# 1.net
KiCad netlist of a schematic drawn in EAGLE
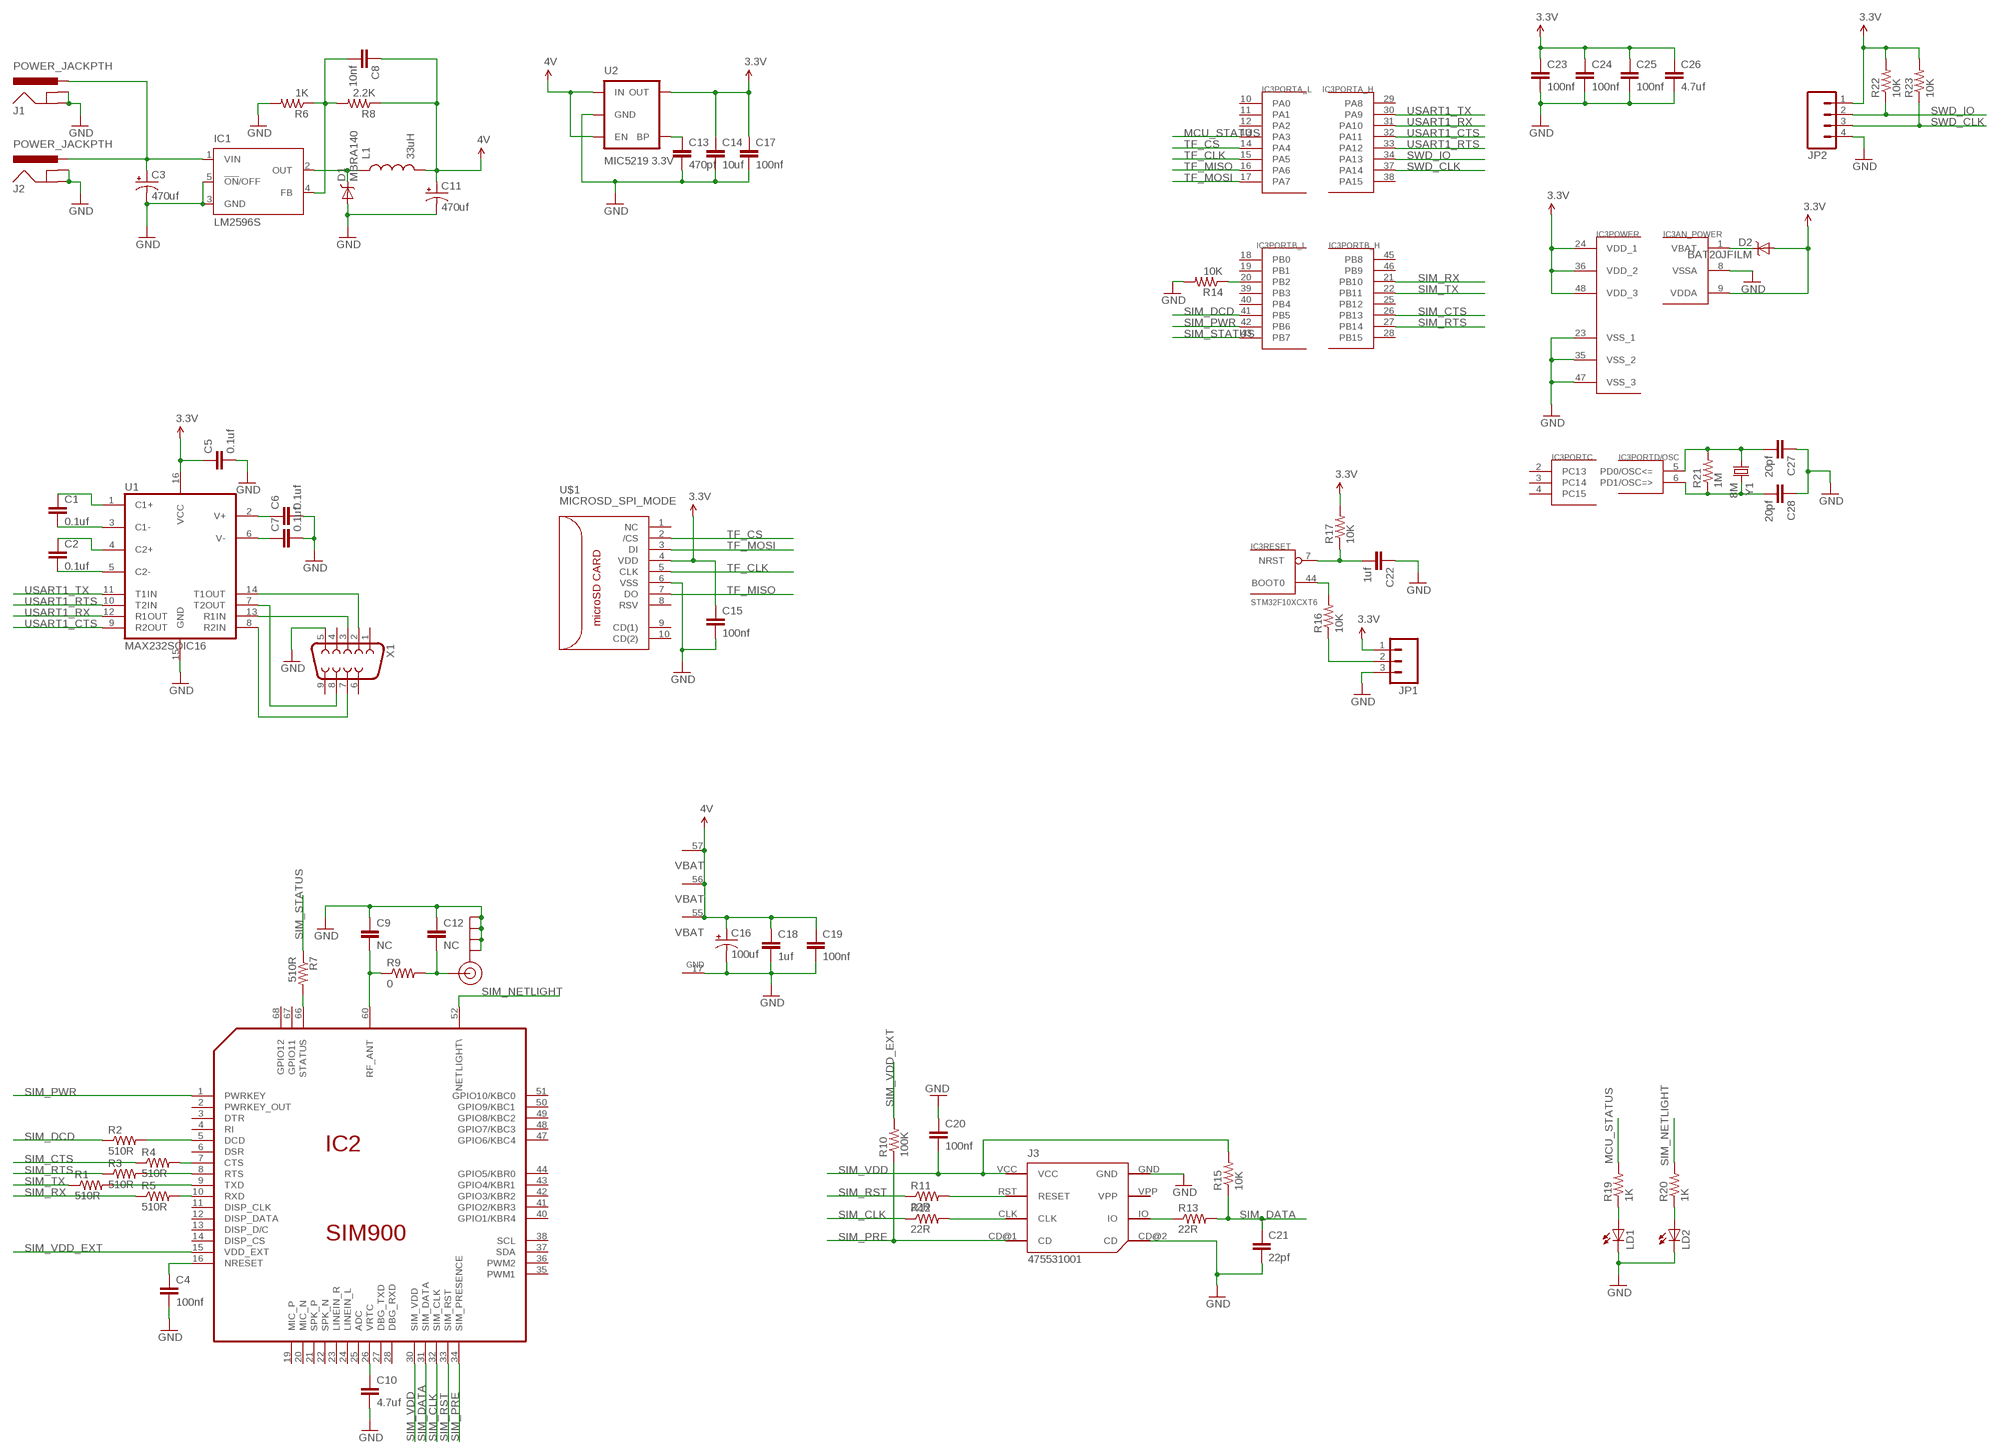
[diagram p0: schematic, sheet 1]

(export (version "E")
  (design (tool "Eeschema 10.0.6"))
  (components
    (comp (ref "C1")
      (value "0.1uf")
      (footprint "eagle-import:0603-CAP")
      (libsource (lib "eagle-import") (part "CAP0603-CAP"))
    )
    (comp (ref "C2")
      (value "0.1uf")
      (footprint "eagle-import:0603-CAP")
      (libsource (lib "eagle-import") (part "CAP0603-CAP"))
    )
    (comp (ref "C3")
      (value "470uf")
      (footprint "eagle-import:PANASONIC_G")
      (libsource (lib "eagle-import") (part "CAP_POLG"))
    )
    (comp (ref "C4")
      (value "100nf")
      (footprint "eagle-import:0603-CAP")
      (libsource (lib "eagle-import") (part "CAP0603-CAP"))
    )
    (comp (ref "C5")
      (value "0.1uf")
      (footprint "eagle-import:0603-CAP")
      (libsource (lib "eagle-import") (part "CAP0603-CAP"))
    )
    (comp (ref "C6")
      (value "0.1uf")
      (footprint "eagle-import:0603-CAP")
      (libsource (lib "eagle-import") (part "CAP0603-CAP"))
    )
    (comp (ref "C7")
      (value "0.1uf")
      (footprint "eagle-import:0603-CAP")
      (libsource (lib "eagle-import") (part "CAP0603-CAP"))
    )
    (comp (ref "C8")
      (value "10nf")
      (footprint "eagle-import:0603-CAP")
      (libsource (lib "eagle-import") (part "CAP0603-CAP"))
    )
    (comp (ref "C9")
      (value "NC")
      (footprint "eagle-import:0603-CAP")
      (libsource (lib "eagle-import") (part "CAP0603-CAP"))
    )
    (comp (ref "C10")
      (value "4.7uf")
      (footprint "eagle-import:0603-CAP")
      (libsource (lib "eagle-import") (part "CAP0603-CAP"))
    )
    (comp (ref "C11")
      (value "470uf")
      (footprint "eagle-import:PANASONIC_G")
      (libsource (lib "eagle-import") (part "CAP_POLG"))
    )
    (comp (ref "C12")
      (value "NC")
      (footprint "eagle-import:0603-CAP")
      (libsource (lib "eagle-import") (part "CAP0603-CAP"))
    )
    (comp (ref "C13")
      (value "470pf")
      (footprint "eagle-import:0603-CAP")
      (libsource (lib "eagle-import") (part "CAP0603-CAP"))
    )
    (comp (ref "C14")
      (value "10uf")
      (footprint "eagle-import:0603-CAP")
      (libsource (lib "eagle-import") (part "CAP0603-CAP"))
    )
    (comp (ref "C15")
      (value "100nf")
      (footprint "eagle-import:0603-CAP")
      (libsource (lib "eagle-import") (part "CAP0603-CAP"))
    )
    (comp (ref "C16")
      (value "100uf")
      (footprint "eagle-import:EIA6032")
      (libsource (lib "eagle-import") (part "SparkFun-Passives_CAP_POL6032"))
    )
    (comp (ref "C17")
      (value "100nf")
      (footprint "eagle-import:0603-CAP")
      (libsource (lib "eagle-import") (part "CAP0603-CAP"))
    )
    (comp (ref "C18")
      (value "1uf")
      (footprint "eagle-import:0603-CAP")
      (libsource (lib "eagle-import") (part "CAP0603-CAP"))
    )
    (comp (ref "C19")
      (value "100nf")
      (footprint "eagle-import:0603-CAP")
      (libsource (lib "eagle-import") (part "CAP0603-CAP"))
    )
    (comp (ref "C20")
      (value "100nf")
      (footprint "eagle-import:0603-CAP")
      (libsource (lib "eagle-import") (part "CAP0603-CAP"))
    )
    (comp (ref "C21")
      (value "22pf")
      (footprint "eagle-import:0603-CAP")
      (libsource (lib "eagle-import") (part "CAP0603-CAP"))
    )
    (comp (ref "C22")
      (value "1uf")
      (footprint "eagle-import:0603-CAP")
      (libsource (lib "eagle-import") (part "CAP0603-CAP"))
    )
    (comp (ref "C23")
      (value "100nf")
      (footprint "eagle-import:0603-CAP")
      (libsource (lib "eagle-import") (part "CAP0603-CAP"))
    )
    (comp (ref "C24")
      (value "100nf")
      (footprint "eagle-import:0603-CAP")
      (libsource (lib "eagle-import") (part "CAP0603-CAP"))
    )
    (comp (ref "C25")
      (value "100nf")
      (footprint "eagle-import:0603-CAP")
      (libsource (lib "eagle-import") (part "CAP0603-CAP"))
    )
    (comp (ref "C26")
      (value "4.7uf")
      (footprint "eagle-import:0603-CAP")
      (libsource (lib "eagle-import") (part "CAP0603-CAP"))
    )
    (comp (ref "C27")
      (value "20pf")
      (footprint "eagle-import:0603-CAP")
      (libsource (lib "eagle-import") (part "CAP0603-CAP"))
    )
    (comp (ref "C28")
      (value "20pf")
      (footprint "eagle-import:0603-CAP")
      (libsource (lib "eagle-import") (part "CAP0603-CAP"))
    )
    (comp (ref "D1")
      (value "MBRA140")
      (footprint "eagle-import:SMA-DIODE")
      (libsource (lib "eagle-import") (part "MBRA140"))
    )
    (comp (ref "D2")
      (value "BAT20JFILM")
      (footprint "eagle-import:SOD-323")
      (libsource (lib "eagle-import") (part "BAT20JFILM"))
    )
    (comp (ref "IC1")
      (value "LM2596S")
      (footprint "eagle-import:TO263-5")
      (libsource (lib "eagle-import") (part "LM2596S"))
    )
    (comp (ref "IC2")
      (value "SIM900")
      (footprint "eagle-import:SIM900")
      (libsource (lib "eagle-import") (part "SIM900"))
    )
    (comp (ref "IC3")
      (value "STM32F10XCXT6")
      (footprint "eagle-import:TQFP48")
      (libsource (lib "eagle-import") (part "STM32F10XCXT6"))
    )
    (comp (ref "J$1")
      (value "SMA_EDGE")
      (footprint "eagle-import:SMA-EDGE")
      (libsource (lib "eagle-import") (part "SMA_EDGE"))
    )
    (comp (ref "J1")
      (value "POWER_JACKPTH")
      (footprint "eagle-import:POWER_JACK_PTH")
      (libsource (lib "eagle-import") (part "POWER_JACKPTH"))
    )
    (comp (ref "J2")
      (value "POWER_JACKPTH")
      (footprint "eagle-import:POWER_JACK_PTH")
      (libsource (lib "eagle-import") (part "POWER_JACKPTH"))
    )
    (comp (ref "J3")
      (value "475531001")
      (footprint "eagle-import:475531001")
      (libsource (lib "eagle-import") (part "475531001"))
    )
    (comp (ref "JP1")
      (value "M03PTH")
      (footprint "eagle-import:1X03")
      (libsource (lib "eagle-import") (part "M03PTH"))
    )
    (comp (ref "JP2")
      (value "M04PTH")
      (footprint "eagle-import:1X04")
      (libsource (lib "eagle-import") (part "M04PTH"))
    )
    (comp (ref "L1")
      (value "33uH")
      (footprint "eagle-import:CR75")
      (libsource (lib "eagle-import") (part "INDUCTOR68UH-1A"))
    )
    (comp (ref "LD1")
      (value "LEDCHIP-LED0805")
      (footprint "eagle-import:CHIP-LED0805")
      (libsource (lib "eagle-import") (part "LEDCHIP-LED0805"))
    )
    (comp (ref "LD2")
      (value "LEDCHIP-LED0805")
      (footprint "eagle-import:CHIP-LED0805")
      (libsource (lib "eagle-import") (part "LEDCHIP-LED0805"))
    )
    (comp (ref "R1")
      (value "510R")
      (footprint "eagle-import:0603-RES")
      (libsource (lib "eagle-import") (part "RESISTOR0603-RES"))
    )
    (comp (ref "R2")
      (value "510R")
      (footprint "eagle-import:0603-RES")
      (libsource (lib "eagle-import") (part "RESISTOR0603-RES"))
    )
    (comp (ref "R3")
      (value "510R")
      (footprint "eagle-import:0603-RES")
      (libsource (lib "eagle-import") (part "RESISTOR0603-RES"))
    )
    (comp (ref "R4")
      (value "510R")
      (footprint "eagle-import:0603-RES")
      (libsource (lib "eagle-import") (part "RESISTOR0603-RES"))
    )
    (comp (ref "R5")
      (value "510R")
      (footprint "eagle-import:0603-RES")
      (libsource (lib "eagle-import") (part "RESISTOR0603-RES"))
    )
    (comp (ref "R6")
      (value "1K")
      (footprint "eagle-import:0603-RES")
      (libsource (lib "eagle-import") (part "RESISTOR0603-RES"))
    )
    (comp (ref "R7")
      (value "510R")
      (footprint "eagle-import:0603-RES")
      (libsource (lib "eagle-import") (part "RESISTOR0603-RES"))
    )
    (comp (ref "R8")
      (value "2.2K")
      (footprint "eagle-import:0603-RES")
      (libsource (lib "eagle-import") (part "RESISTOR0603-RES"))
    )
    (comp (ref "R9")
      (value "0")
      (footprint "eagle-import:0603-RES")
      (libsource (lib "eagle-import") (part "1M-1%"))
    )
    (comp (ref "R10")
      (value "100K")
      (footprint "eagle-import:0603-RES")
      (libsource (lib "eagle-import") (part "1M-1%"))
    )
    (comp (ref "R11")
      (value "22R")
      (footprint "eagle-import:0603-RES")
      (libsource (lib "eagle-import") (part "1M-1%"))
    )
    (comp (ref "R12")
      (value "22R")
      (footprint "eagle-import:0603-RES")
      (libsource (lib "eagle-import") (part "1M-1%"))
    )
    (comp (ref "R13")
      (value "22R")
      (footprint "eagle-import:0603-RES")
      (libsource (lib "eagle-import") (part "1M-1%"))
    )
    (comp (ref "R14")
      (value "10K")
      (footprint "eagle-import:0603-RES")
      (libsource (lib "eagle-import") (part "1M-1%"))
    )
    (comp (ref "R15")
      (value "10K")
      (footprint "eagle-import:0603-RES")
      (libsource (lib "eagle-import") (part "1M-1%"))
    )
    (comp (ref "R16")
      (value "10K")
      (footprint "eagle-import:0603-RES")
      (libsource (lib "eagle-import") (part "RESISTOR0603-RES"))
    )
    (comp (ref "R17")
      (value "10K")
      (footprint "eagle-import:0603-RES")
      (libsource (lib "eagle-import") (part "RESISTOR0603-RES"))
    )
    (comp (ref "R19")
      (value "1K")
      (footprint "eagle-import:0603-RES")
      (libsource (lib "eagle-import") (part "RESISTOR0603-RES"))
    )
    (comp (ref "R20")
      (value "1K")
      (footprint "eagle-import:0603-RES")
      (libsource (lib "eagle-import") (part "RESISTOR0603-RES"))
    )
    (comp (ref "R21")
      (value "1M")
      (footprint "eagle-import:0603-RES")
      (libsource (lib "eagle-import") (part "1M-1%"))
    )
    (comp (ref "R22")
      (value "10K")
      (footprint "eagle-import:0603-RES")
      (libsource (lib "eagle-import") (part "1M-1%"))
    )
    (comp (ref "R23")
      (value "10K")
      (footprint "eagle-import:0603-RES")
      (libsource (lib "eagle-import") (part "1M-1%"))
    )
    (comp (ref "U$1")
      (value "MICROSD_SPI_MODE")
      (footprint "eagle-import:MICRO_SD_CONNECTOR")
      (libsource (lib "eagle-import") (part "MICROSD_SPI_MODE"))
    )
    (comp (ref "U1")
      (value "MAX232SOIC16")
      (footprint "eagle-import:SO016")
      (libsource (lib "eagle-import") (part "MAX232SOIC16"))
    )
    (comp (ref "U2")
      (value "MIC5219 3.3V")
      (footprint "eagle-import:SOT23-5")
      (libsource (lib "eagle-import") (part "V_REG_MIC52193.3V"))
    )
    (comp (ref "X1")
      (value "DB9FEMALE")
      (footprint "eagle-import:DB9")
      (libsource (lib "eagle-import") (part "DB9FEMALE"))
    )
    (comp (ref "Y1")
      (value "8M")
      (footprint "eagle-import:HC49US")
      (libsource (lib "eagle-import") (part "CRYSTALHC49US"))
    )
  )
  (nets
    (net (code "1") (name "/MCU_STATUS") (class "Default")
      (node (ref "IC3") (pin "13") (pinfunction "PA3_13") (pintype "bidirectional"))
      (node (ref "R19") (pin "2") (pinfunction "2_2") (pintype "passive"))
    )
    (net (code "2") (name "/SIM_CLK") (class "Default")
      (node (ref "IC2") (pin "32") (pinfunction "SIM_CLK_32") (pintype "bidirectional"))
      (node (ref "R12") (pin "1") (pinfunction "1_1") (pintype "passive"))
    )
    (net (code "3") (name "/SIM_CTS") (class "Default")
      (node (ref "IC3") (pin "26") (pinfunction "PB13_26") (pintype "bidirectional"))
      (node (ref "R4") (pin "1") (pinfunction "1_1") (pintype "passive"))
    )
    (net (code "4") (name "/SIM_DATA") (class "Default")
      (node (ref "C21") (pin "1") (pinfunction "1_1") (pintype "passive"))
      (node (ref "IC2") (pin "31") (pinfunction "SIM_DATA_31") (pintype "bidirectional"))
      (node (ref "R13") (pin "2") (pinfunction "2_2") (pintype "passive"))
      (node (ref "R15") (pin "1") (pinfunction "1_1") (pintype "passive"))
    )
    (net (code "5") (name "/SIM_DCD") (class "Default")
      (node (ref "IC3") (pin "41") (pinfunction "PB5_41") (pintype "bidirectional"))
      (node (ref "R2") (pin "1") (pinfunction "1_1") (pintype "passive"))
    )
    (net (code "6") (name "/SIM_NETLIGHT") (class "Default")
      (node (ref "IC2") (pin "52") (pinfunction "NETLIGHT\\_52") (pintype "bidirectional"))
      (node (ref "R20") (pin "2") (pinfunction "2_2") (pintype "passive"))
    )
    (net (code "7") (name "/SIM_PRE") (class "Default")
      (node (ref "IC2") (pin "34") (pinfunction "SIM_PRESENCE_34") (pintype "bidirectional"))
      (node (ref "J3") (pin "CD@1") (pinfunction "CD_CD@1") (pintype "bidirectional"))
      (node (ref "R10") (pin "1") (pinfunction "1_1") (pintype "passive"))
    )
    (net (code "8") (name "/SIM_PWR") (class "Default")
      (node (ref "IC2") (pin "1") (pinfunction "PWRKEY_1") (pintype "bidirectional"))
      (node (ref "IC3") (pin "42") (pinfunction "PB6_42") (pintype "bidirectional"))
    )
    (net (code "9") (name "/SIM_RST") (class "Default")
      (node (ref "IC2") (pin "33") (pinfunction "SIM_RST_33") (pintype "bidirectional"))
      (node (ref "R11") (pin "1") (pinfunction "1_1") (pintype "passive"))
    )
    (net (code "10") (name "/SIM_RTS") (class "Default")
      (node (ref "IC3") (pin "27") (pinfunction "PB14_27") (pintype "bidirectional"))
      (node (ref "R3") (pin "1") (pinfunction "1_1") (pintype "passive"))
    )
    (net (code "11") (name "/SIM_RX") (class "Default")
      (node (ref "IC3") (pin "21") (pinfunction "PB10_21") (pintype "bidirectional"))
      (node (ref "R5") (pin "1") (pinfunction "1_1") (pintype "passive"))
    )
    (net (code "12") (name "/SIM_STATUS") (class "Default")
      (node (ref "IC3") (pin "43") (pinfunction "PB7_43") (pintype "bidirectional"))
      (node (ref "R7") (pin "1") (pinfunction "1_1") (pintype "passive"))
    )
    (net (code "13") (name "/SIM_TX") (class "Default")
      (node (ref "IC3") (pin "22") (pinfunction "PB11_22") (pintype "bidirectional"))
      (node (ref "R1") (pin "1") (pinfunction "1_1") (pintype "passive"))
    )
    (net (code "14") (name "/SIM_VDD") (class "Default")
      (node (ref "C20") (pin "2") (pinfunction "2_2") (pintype "passive"))
      (node (ref "IC2") (pin "30") (pinfunction "SIM_VDD_30") (pintype "bidirectional"))
      (node (ref "J3") (pin "VCC") (pinfunction "VCC_VCC") (pintype "bidirectional"))
      (node (ref "R15") (pin "2") (pinfunction "2_2") (pintype "passive"))
    )
    (net (code "15") (name "/SIM_VDD_EXT") (class "Default")
      (node (ref "IC2") (pin "15") (pinfunction "VDD_EXT_15") (pintype "bidirectional"))
      (node (ref "R10") (pin "2") (pinfunction "2_2") (pintype "passive"))
    )
    (net (code "16") (name "/SWD_CLK") (class "Default")
      (node (ref "IC3") (pin "37") (pinfunction "PA14_37") (pintype "bidirectional"))
      (node (ref "JP2") (pin "3") (pinfunction "3_3") (pintype "passive"))
      (node (ref "R23") (pin "1") (pinfunction "1_1") (pintype "passive"))
    )
    (net (code "17") (name "/SWD_IO") (class "Default")
      (node (ref "IC3") (pin "34") (pinfunction "PA13_34") (pintype "bidirectional"))
      (node (ref "JP2") (pin "2") (pinfunction "2_2") (pintype "passive"))
      (node (ref "R22") (pin "1") (pinfunction "1_1") (pintype "passive"))
    )
    (net (code "18") (name "/TF_CLK") (class "Default")
      (node (ref "IC3") (pin "15") (pinfunction "PA5_15") (pintype "bidirectional"))
      (node (ref "U$1") (pin "5") (pinfunction "CLK_5") (pintype "bidirectional"))
    )
    (net (code "19") (name "/TF_CS") (class "Default")
      (node (ref "IC3") (pin "14") (pinfunction "PA4_14") (pintype "bidirectional"))
      (node (ref "U$1") (pin "2") (pinfunction "/CS_2") (pintype "bidirectional"))
    )
    (net (code "20") (name "/TF_MISO") (class "Default")
      (node (ref "IC3") (pin "16") (pinfunction "PA6_16") (pintype "bidirectional"))
      (node (ref "U$1") (pin "7") (pinfunction "DO_7") (pintype "bidirectional"))
    )
    (net (code "21") (name "/TF_MOSI") (class "Default")
      (node (ref "IC3") (pin "17") (pinfunction "PA7_17") (pintype "bidirectional"))
      (node (ref "U$1") (pin "3") (pinfunction "DI_3") (pintype "bidirectional"))
    )
    (net (code "22") (name "/USART1_CTS") (class "Default")
      (node (ref "IC3") (pin "32") (pinfunction "PA11_32") (pintype "bidirectional"))
      (node (ref "U1") (pin "9") (pinfunction "R2OUT_9") (pintype "output"))
    )
    (net (code "23") (name "/USART1_RTS") (class "Default")
      (node (ref "IC3") (pin "33") (pinfunction "PA12_33") (pintype "bidirectional"))
      (node (ref "U1") (pin "10") (pinfunction "T2IN_10") (pintype "input"))
    )
    (net (code "24") (name "/USART1_RX") (class "Default")
      (node (ref "IC3") (pin "31") (pinfunction "PA10_31") (pintype "bidirectional"))
      (node (ref "U1") (pin "12") (pinfunction "R1OUT_12") (pintype "output"))
    )
    (net (code "25") (name "/USART1_TX") (class "Default")
      (node (ref "IC3") (pin "30") (pinfunction "PA9_30") (pintype "bidirectional"))
      (node (ref "U1") (pin "11") (pinfunction "T1IN_11") (pintype "input"))
    )
    (net (code "26") (name "3.3V") (class "Default")
      (node (ref "C14") (pin "1") (pinfunction "1_1") (pintype "passive"))
      (node (ref "C15") (pin "1") (pinfunction "1_1") (pintype "passive"))
      (node (ref "C17") (pin "1") (pinfunction "1_1") (pintype "passive"))
      (node (ref "C23") (pin "1") (pinfunction "1_1") (pintype "passive"))
      (node (ref "C24") (pin "1") (pinfunction "1_1") (pintype "passive"))
      (node (ref "C25") (pin "1") (pinfunction "1_1") (pintype "passive"))
      (node (ref "C26") (pin "1") (pinfunction "1_1") (pintype "passive"))
      (node (ref "C5") (pin "1") (pinfunction "1_1") (pintype "passive"))
      (node (ref "D2") (pin "2") (pinfunction "A_2") (pintype "passive"))
      (node (ref "IC3") (pin "24") (pinfunction "VDD_1_24") (pintype "power_in"))
      (node (ref "IC3") (pin "36") (pinfunction "VDD_2_36") (pintype "power_in"))
      (node (ref "IC3") (pin "48") (pinfunction "VDD_3_48") (pintype "power_in"))
      (node (ref "IC3") (pin "9") (pinfunction "VDDA_9") (pintype "power_in"))
      (node (ref "JP1") (pin "1") (pinfunction "1_1") (pintype "passive"))
      (node (ref "JP2") (pin "1") (pinfunction "1_1") (pintype "passive"))
      (node (ref "R17") (pin "2") (pinfunction "2_2") (pintype "passive"))
      (node (ref "R22") (pin "2") (pinfunction "2_2") (pintype "passive"))
      (node (ref "R23") (pin "2") (pinfunction "2_2") (pintype "passive"))
      (node (ref "U$1") (pin "4") (pinfunction "VDD_4") (pintype "bidirectional"))
      (node (ref "U1") (pin "16") (pinfunction "VCC_16") (pintype "bidirectional"))
      (node (ref "U2") (pin "5") (pinfunction "OUT_5") (pintype "passive"))
    )
    (net (code "27") (name "4V") (class "Default")
      (node (ref "C11") (pin "+") (pinfunction "+_+") (pintype "passive"))
      (node (ref "C16") (pin "P$1") (pinfunction "+_P$1") (pintype "passive"))
      (node (ref "C18") (pin "1") (pinfunction "1_1") (pintype "passive"))
      (node (ref "C19") (pin "1") (pinfunction "1_1") (pintype "passive"))
      (node (ref "C8") (pin "1") (pinfunction "1_1") (pintype "passive"))
      (node (ref "IC2") (pin "55") (pinfunction "VBAT_55") (pintype "power_in"))
      (node (ref "IC2") (pin "56") (pinfunction "VBAT_56") (pintype "power_in"))
      (node (ref "IC2") (pin "57") (pinfunction "VBAT_57") (pintype "power_in"))
      (node (ref "L1") (pin "P$2") (pinfunction "2_P$2") (pintype "passive"))
      (node (ref "R8") (pin "1") (pinfunction "1_1") (pintype "passive"))
      (node (ref "U2") (pin "1") (pinfunction "IN_1") (pintype "input"))
      (node (ref "U2") (pin "3") (pinfunction "EN_3") (pintype "input"))
    )
    (net (code "28") (name "GND") (class "Default")
      (node (ref "C10") (pin "2") (pinfunction "2_2") (pintype "passive"))
      (node (ref "C11") (pin "-") (pinfunction "-_-") (pintype "passive"))
      (node (ref "C12") (pin "1") (pinfunction "1_1") (pintype "passive"))
      (node (ref "C13") (pin "2") (pinfunction "2_2") (pintype "passive"))
      (node (ref "C14") (pin "2") (pinfunction "2_2") (pintype "passive"))
      (node (ref "C15") (pin "2") (pinfunction "2_2") (pintype "passive"))
      (node (ref "C16") (pin "P$2") (pinfunction "-_P$2") (pintype "passive"))
      (node (ref "C17") (pin "2") (pinfunction "2_2") (pintype "passive"))
      (node (ref "C18") (pin "2") (pinfunction "2_2") (pintype "passive"))
      (node (ref "C19") (pin "2") (pinfunction "2_2") (pintype "passive"))
      (node (ref "C20") (pin "1") (pinfunction "1_1") (pintype "passive"))
      (node (ref "C21") (pin "2") (pinfunction "2_2") (pintype "passive"))
      (node (ref "C22") (pin "1") (pinfunction "1_1") (pintype "passive"))
      (node (ref "C23") (pin "2") (pinfunction "2_2") (pintype "passive"))
      (node (ref "C24") (pin "2") (pinfunction "2_2") (pintype "passive"))
      (node (ref "C25") (pin "2") (pinfunction "2_2") (pintype "passive"))
      (node (ref "C26") (pin "2") (pinfunction "2_2") (pintype "passive"))
      (node (ref "C27") (pin "1") (pinfunction "1_1") (pintype "passive"))
      (node (ref "C28") (pin "1") (pinfunction "1_1") (pintype "passive"))
      (node (ref "C3") (pin "-") (pinfunction "-_-") (pintype "passive"))
      (node (ref "C4") (pin "2") (pinfunction "2_2") (pintype "passive"))
      (node (ref "C5") (pin "2") (pinfunction "2_2") (pintype "passive"))
      (node (ref "C6") (pin "2") (pinfunction "2_2") (pintype "passive"))
      (node (ref "C7") (pin "2") (pinfunction "2_2") (pintype "passive"))
      (node (ref "C9") (pin "1") (pinfunction "1_1") (pintype "passive"))
      (node (ref "D1") (pin "A") (pinfunction "A_A") (pintype "passive"))
      (node (ref "IC1") (pin "3") (pinfunction "GND_3") (pintype "power_in"))
      (node (ref "IC1") (pin "5") (pinfunction "~{ON}/OFF_5") (pintype "input"))
      (node (ref "IC2") (pin "17") (pinfunction "GND_17") (pintype "power_in"))
      (node (ref "IC3") (pin "23") (pinfunction "VSS_1_23") (pintype "power_in"))
      (node (ref "IC3") (pin "35") (pinfunction "VSS_2_35") (pintype "power_in"))
      (node (ref "IC3") (pin "47") (pinfunction "VSS_3_47") (pintype "power_in"))
      (node (ref "IC3") (pin "8") (pinfunction "VSSA_8") (pintype "power_in"))
      (node (ref "J$1") (pin "GND@0") (pinfunction "GND_GND@0") (pintype "bidirectional"))
      (node (ref "J$1") (pin "GND@1") (pinfunction "GND_GND@1") (pintype "bidirectional"))
      (node (ref "J$1") (pin "GND@2") (pinfunction "GND_GND@2") (pintype "bidirectional"))
      (node (ref "J$1") (pin "GND@3") (pinfunction "GND_GND@3") (pintype "bidirectional"))
      (node (ref "J1") (pin "GND") (pinfunction "GND_GND") (pintype "bidirectional"))
      (node (ref "J1") (pin "GNDBREAK") (pinfunction "GNDBREAK_GNDBREAK") (pintype "bidirectional"))
      (node (ref "J2") (pin "GND") (pinfunction "GND_GND") (pintype "bidirectional"))
      (node (ref "J2") (pin "GNDBREAK") (pinfunction "GNDBREAK_GNDBREAK") (pintype "bidirectional"))
      (node (ref "J3") (pin "CD@2") (pinfunction "CD_CD@2") (pintype "bidirectional"))
      (node (ref "J3") (pin "GND") (pinfunction "GND_GND") (pintype "bidirectional"))
      (node (ref "JP1") (pin "3") (pinfunction "3_3") (pintype "passive"))
      (node (ref "JP2") (pin "4") (pinfunction "4_4") (pintype "passive"))
      (node (ref "LD1") (pin "C") (pinfunction "C_C") (pintype "passive"))
      (node (ref "LD2") (pin "C") (pinfunction "C_C") (pintype "passive"))
      (node (ref "R14") (pin "2") (pinfunction "2_2") (pintype "passive"))
      (node (ref "R6") (pin "2") (pinfunction "2_2") (pintype "passive"))
      (node (ref "U$1") (pin "6") (pinfunction "VSS_6") (pintype "bidirectional"))
      (node (ref "U1") (pin "15") (pinfunction "GND_15") (pintype "bidirectional"))
      (node (ref "U2") (pin "2") (pinfunction "GND_2") (pintype "input"))
      (node (ref "X1") (pin "5") (pinfunction "5_5") (pintype "passive"))
    )
    (net (code "29") (name "Net-(D2-C)") (class "Default")
      (node (ref "D2") (pin "1") (pinfunction "C_1") (pintype "passive"))
      (node (ref "IC3") (pin "1") (pinfunction "VBAT_1") (pintype "power_in"))
    )
    (net (code "30") (name "Net-(IC1-FB)") (class "Default")
      (node (ref "C8") (pin "2") (pinfunction "2_2") (pintype "passive"))
      (node (ref "IC1") (pin "4") (pinfunction "FB_4") (pintype "input"))
      (node (ref "R6") (pin "1") (pinfunction "1_1") (pintype "passive"))
      (node (ref "R8") (pin "2") (pinfunction "2_2") (pintype "passive"))
    )
    (net (code "31") (name "Net-(IC1-OUT)") (class "Default")
      (node (ref "D1") (pin "C") (pinfunction "C_C") (pintype "passive"))
      (node (ref "IC1") (pin "2") (pinfunction "OUT_2") (pintype "output"))
      (node (ref "L1") (pin "P$1") (pinfunction "1_P$1") (pintype "passive"))
    )
    (net (code "32") (name "Net-(IC1-VIN)") (class "Default")
      (node (ref "C3") (pin "+") (pinfunction "+_+") (pintype "passive"))
      (node (ref "IC1") (pin "1") (pinfunction "VIN_1") (pintype "input"))
      (node (ref "J1") (pin "PWR") (pinfunction "PWR_PWR") (pintype "bidirectional"))
      (node (ref "J2") (pin "PWR") (pinfunction "PWR_PWR") (pintype "bidirectional"))
    )
    (net (code "33") (name "Net-(IC2A-CTS)") (class "Default")
      (node (ref "IC2") (pin "7") (pinfunction "CTS_7") (pintype "bidirectional"))
      (node (ref "R4") (pin "2") (pinfunction "2_2") (pintype "passive"))
    )
    (net (code "34") (name "Net-(IC2A-DCD)") (class "Default")
      (node (ref "IC2") (pin "5") (pinfunction "DCD_5") (pintype "bidirectional"))
      (node (ref "R2") (pin "2") (pinfunction "2_2") (pintype "passive"))
    )
    (net (code "35") (name "Net-(IC2A-NRESET)") (class "Default")
      (node (ref "C4") (pin "1") (pinfunction "1_1") (pintype "passive"))
      (node (ref "IC2") (pin "16") (pinfunction "NRESET_16") (pintype "bidirectional"))
    )
    (net (code "36") (name "Net-(IC2A-RF_ANT)") (class "Default")
      (node (ref "C9") (pin "2") (pinfunction "2_2") (pintype "passive"))
      (node (ref "IC2") (pin "60") (pinfunction "RF_ANT_60") (pintype "bidirectional"))
      (node (ref "R9") (pin "1") (pinfunction "1_1") (pintype "passive"))
    )
    (net (code "37") (name "Net-(IC2A-RTS)") (class "Default")
      (node (ref "IC2") (pin "8") (pinfunction "RTS_8") (pintype "bidirectional"))
      (node (ref "R3") (pin "2") (pinfunction "2_2") (pintype "passive"))
    )
    (net (code "38") (name "Net-(IC2A-RXD)") (class "Default")
      (node (ref "IC2") (pin "10") (pinfunction "RXD_10") (pintype "bidirectional"))
      (node (ref "R5") (pin "2") (pinfunction "2_2") (pintype "passive"))
    )
    (net (code "39") (name "Net-(IC2A-STATUS)") (class "Default")
      (node (ref "IC2") (pin "66") (pinfunction "STATUS_66") (pintype "bidirectional"))
      (node (ref "R7") (pin "2") (pinfunction "2_2") (pintype "passive"))
    )
    (net (code "40") (name "Net-(IC2A-TXD)") (class "Default")
      (node (ref "IC2") (pin "9") (pinfunction "TXD_9") (pintype "bidirectional"))
      (node (ref "R1") (pin "2") (pinfunction "2_2") (pintype "passive"))
    )
    (net (code "41") (name "Net-(IC2A-VRTC)") (class "Default")
      (node (ref "C10") (pin "1") (pinfunction "1_1") (pintype "passive"))
      (node (ref "IC2") (pin "26") (pinfunction "VRTC_26") (pintype "bidirectional"))
    )
    (net (code "42") (name "Net-(IC3E-PB2)") (class "Default")
      (node (ref "IC3") (pin "20") (pinfunction "PB2_20") (pintype "bidirectional"))
      (node (ref "R14") (pin "1") (pinfunction "1_1") (pintype "passive"))
    )
    (net (code "43") (name "Net-(IC3G-PD0{slash}OSC<=)") (class "Default")
      (node (ref "C27") (pin "2") (pinfunction "2_2") (pintype "passive"))
      (node (ref "IC3") (pin "5") (pinfunction "PD0/OSC<=_5") (pintype "bidirectional"))
      (node (ref "R21") (pin "2") (pinfunction "2_2") (pintype "passive"))
      (node (ref "Y1") (pin "1") (pinfunction "1_1") (pintype "passive"))
    )
    (net (code "44") (name "Net-(IC3G-PD1{slash}OSC=>)") (class "Default")
      (node (ref "C28") (pin "2") (pinfunction "2_2") (pintype "passive"))
      (node (ref "IC3") (pin "6") (pinfunction "PD1/OSC=>_6") (pintype "bidirectional"))
      (node (ref "R21") (pin "1") (pinfunction "1_1") (pintype "passive"))
      (node (ref "Y1") (pin "2") (pinfunction "2_2") (pintype "passive"))
    )
    (net (code "45") (name "Net-(IC3I-BOOT0)") (class "Default")
      (node (ref "IC3") (pin "44") (pinfunction "BOOT0_44") (pintype "input"))
      (node (ref "R16") (pin "2") (pinfunction "2_2") (pintype "passive"))
    )
    (net (code "46") (name "Net-(IC3I-NRST)") (class "Default")
      (node (ref "C22") (pin "2") (pinfunction "2_2") (pintype "passive"))
      (node (ref "IC3") (pin "7") (pinfunction "NRST_7") (pintype "input"))
      (node (ref "R17") (pin "1") (pinfunction "1_1") (pintype "passive"))
    )
    (net (code "47") (name "Net-(J$1-SIGNAL)") (class "Default")
      (node (ref "C12") (pin "2") (pinfunction "2_2") (pintype "passive"))
      (node (ref "J$1") (pin "SIG") (pinfunction "SIGNAL_SIG") (pintype "bidirectional"))
      (node (ref "R9") (pin "2") (pinfunction "2_2") (pintype "passive"))
    )
    (net (code "48") (name "Net-(J3-PadCLK)") (class "Default")
      (node (ref "J3") (pin "CLK") (pinfunction "CLK_CLK") (pintype "bidirectional"))
      (node (ref "R12") (pin "2") (pinfunction "2_2") (pintype "passive"))
    )
    (net (code "49") (name "Net-(J3-PadIO)") (class "Default")
      (node (ref "J3") (pin "IO") (pinfunction "IO_IO") (pintype "bidirectional"))
      (node (ref "R13") (pin "1") (pinfunction "1_1") (pintype "passive"))
    )
    (net (code "50") (name "Net-(J3-RESET)") (class "Default")
      (node (ref "J3") (pin "RST") (pinfunction "RESET_RST") (pintype "bidirectional"))
      (node (ref "R11") (pin "2") (pinfunction "2_2") (pintype "passive"))
    )
    (net (code "51") (name "Net-(JP1-Pad2)") (class "Default")
      (node (ref "JP1") (pin "2") (pinfunction "2_2") (pintype "passive"))
      (node (ref "R16") (pin "1") (pinfunction "1_1") (pintype "passive"))
    )
    (net (code "52") (name "Net-(LD1-PadA)") (class "Default")
      (node (ref "LD1") (pin "A") (pinfunction "A_A") (pintype "passive"))
      (node (ref "R19") (pin "1") (pinfunction "1_1") (pintype "passive"))
    )
    (net (code "53") (name "Net-(LD2-PadA)") (class "Default")
      (node (ref "LD2") (pin "A") (pinfunction "A_A") (pintype "passive"))
      (node (ref "R20") (pin "1") (pinfunction "1_1") (pintype "passive"))
    )
    (net (code "54") (name "Net-(U1-C1+)") (class "Default")
      (node (ref "C1") (pin "1") (pinfunction "1_1") (pintype "passive"))
      (node (ref "U1") (pin "1") (pinfunction "C1+_1") (pintype "bidirectional"))
    )
    (net (code "55") (name "Net-(U1-C1-)") (class "Default")
      (node (ref "C1") (pin "2") (pinfunction "2_2") (pintype "passive"))
      (node (ref "U1") (pin "3") (pinfunction "C1-_3") (pintype "bidirectional"))
    )
    (net (code "56") (name "Net-(U1-C2+)") (class "Default")
      (node (ref "C2") (pin "1") (pinfunction "1_1") (pintype "passive"))
      (node (ref "U1") (pin "4") (pinfunction "C2+_4") (pintype "bidirectional"))
    )
    (net (code "57") (name "Net-(U1-C2-)") (class "Default")
      (node (ref "C2") (pin "2") (pinfunction "2_2") (pintype "passive"))
      (node (ref "U1") (pin "5") (pinfunction "C2-_5") (pintype "bidirectional"))
    )
    (net (code "58") (name "Net-(U1-R1IN)") (class "Default")
      (node (ref "U1") (pin "13") (pinfunction "R1IN_13") (pintype "input"))
      (node (ref "X1") (pin "3") (pinfunction "3_3") (pintype "passive"))
    )
    (net (code "59") (name "Net-(U1-R2IN)") (class "Default")
      (node (ref "U1") (pin "8") (pinfunction "R2IN_8") (pintype "input"))
      (node (ref "X1") (pin "7") (pinfunction "7_7") (pintype "passive"))
    )
    (net (code "60") (name "Net-(U1-T1OUT)") (class "Default")
      (node (ref "U1") (pin "14") (pinfunction "T1OUT_14") (pintype "output"))
      (node (ref "X1") (pin "2") (pinfunction "2_2") (pintype "passive"))
    )
    (net (code "61") (name "Net-(U1-T2OUT)") (class "Default")
      (node (ref "U1") (pin "7") (pinfunction "T2OUT_7") (pintype "output"))
      (node (ref "X1") (pin "8") (pinfunction "8_8") (pintype "passive"))
    )
    (net (code "62") (name "Net-(U1-V+)") (class "Default")
      (node (ref "C6") (pin "1") (pinfunction "1_1") (pintype "passive"))
      (node (ref "U1") (pin "2") (pinfunction "V+_2") (pintype "bidirectional"))
    )
    (net (code "63") (name "Net-(U1-V-)") (class "Default")
      (node (ref "C7") (pin "1") (pinfunction "1_1") (pintype "passive"))
      (node (ref "U1") (pin "6") (pinfunction "V-_6") (pintype "bidirectional"))
    )
    (net (code "64") (name "Net-(U2-BP)") (class "Default")
      (node (ref "C13") (pin "1") (pinfunction "1_1") (pintype "passive"))
      (node (ref "U2") (pin "4") (pinfunction "BP_4") (pintype "input"))
    )
    (net (code "65") (name "unconnected-(IC2A-ADC-Pad25)") (class "Default")
      (node (ref "IC2") (pin "25") (pinfunction "ADC_25") (pintype "bidirectional"))
    )
    (net (code "66") (name "unconnected-(IC2A-DBG_RXD-Pad28)") (class "Default")
      (node (ref "IC2") (pin "28") (pinfunction "DBG_RXD_28") (pintype "bidirectional"))
    )
    (net (code "67") (name "unconnected-(IC2A-DBG_TXD-Pad27)") (class "Default")
      (node (ref "IC2") (pin "27") (pinfunction "DBG_TXD_27") (pintype "bidirectional"))
    )
    (net (code "68") (name "unconnected-(IC2A-DISP_CLK-Pad11)") (class "Default")
      (node (ref "IC2") (pin "11") (pinfunction "DISP_CLK_11") (pintype "bidirectional"))
    )
    (net (code "69") (name "unconnected-(IC2A-DISP_CS-Pad14)") (class "Default")
      (node (ref "IC2") (pin "14") (pinfunction "DISP_CS_14") (pintype "bidirectional"))
    )
    (net (code "70") (name "unconnected-(IC2A-DISP_DATA-Pad12)") (class "Default")
      (node (ref "IC2") (pin "12") (pinfunction "DISP_DATA_12") (pintype "bidirectional"))
    )
    (net (code "71") (name "unconnected-(IC2A-DISP_D{slash}C-Pad13)") (class "Default")
      (node (ref "IC2") (pin "13") (pinfunction "DISP_D/C_13") (pintype "bidirectional"))
    )
    (net (code "72") (name "unconnected-(IC2A-DSR-Pad6)") (class "Default")
      (node (ref "IC2") (pin "6") (pinfunction "DSR_6") (pintype "bidirectional"))
    )
    (net (code "73") (name "unconnected-(IC2A-DTR-Pad3)") (class "Default")
      (node (ref "IC2") (pin "3") (pinfunction "DTR_3") (pintype "bidirectional"))
    )
    (net (code "74") (name "unconnected-(IC2A-GPIO1{slash}KBR4-Pad40)") (class "Default")
      (node (ref "IC2") (pin "40") (pinfunction "GPIO1/KBR4_40") (pintype "bidirectional"))
    )
    (net (code "75") (name "unconnected-(IC2A-GPIO2{slash}KBR3-Pad41)") (class "Default")
      (node (ref "IC2") (pin "41") (pinfunction "GPIO2/KBR3_41") (pintype "bidirectional"))
    )
    (net (code "76") (name "unconnected-(IC2A-GPIO3{slash}KBR2-Pad42)") (class "Default")
      (node (ref "IC2") (pin "42") (pinfunction "GPIO3/KBR2_42") (pintype "bidirectional"))
    )
    (net (code "77") (name "unconnected-(IC2A-GPIO4{slash}KBR1-Pad43)") (class "Default")
      (node (ref "IC2") (pin "43") (pinfunction "GPIO4/KBR1_43") (pintype "bidirectional"))
    )
    (net (code "78") (name "unconnected-(IC2A-GPIO5{slash}KBR0-Pad44)") (class "Default")
      (node (ref "IC2") (pin "44") (pinfunction "GPIO5/KBR0_44") (pintype "bidirectional"))
    )
    (net (code "79") (name "unconnected-(IC2A-GPIO6{slash}KBC4-Pad47)") (class "Default")
      (node (ref "IC2") (pin "47") (pinfunction "GPIO6/KBC4_47") (pintype "bidirectional"))
    )
    (net (code "80") (name "unconnected-(IC2A-GPIO7{slash}KBC3-Pad48)") (class "Default")
      (node (ref "IC2") (pin "48") (pinfunction "GPIO7/KBC3_48") (pintype "bidirectional"))
    )
    (net (code "81") (name "unconnected-(IC2A-GPIO8{slash}KBC2-Pad49)") (class "Default")
      (node (ref "IC2") (pin "49") (pinfunction "GPIO8/KBC2_49") (pintype "bidirectional"))
    )
    (net (code "82") (name "unconnected-(IC2A-GPIO9{slash}KBC1-Pad50)") (class "Default")
      (node (ref "IC2") (pin "50") (pinfunction "GPIO9/KBC1_50") (pintype "bidirectional"))
    )
    (net (code "83") (name "unconnected-(IC2A-GPIO10{slash}KBC0-Pad51)") (class "Default")
      (node (ref "IC2") (pin "51") (pinfunction "GPIO10/KBC0_51") (pintype "bidirectional"))
    )
    (net (code "84") (name "unconnected-(IC2A-GPIO11-Pad67)") (class "Default")
      (node (ref "IC2") (pin "67") (pinfunction "GPIO11_67") (pintype "bidirectional"))
    )
    (net (code "85") (name "unconnected-(IC2A-GPIO12-Pad68)") (class "Default")
      (node (ref "IC2") (pin "68") (pinfunction "GPIO12_68") (pintype "bidirectional"))
    )
    (net (code "86") (name "unconnected-(IC2A-LINEIN_L-Pad24)") (class "Default")
      (node (ref "IC2") (pin "24") (pinfunction "LINEIN_L_24") (pintype "bidirectional"))
    )
    (net (code "87") (name "unconnected-(IC2A-LINEIN_R-Pad23)") (class "Default")
      (node (ref "IC2") (pin "23") (pinfunction "LINEIN_R_23") (pintype "bidirectional"))
    )
    (net (code "88") (name "unconnected-(IC2A-MIC_N-Pad20)") (class "Default")
      (node (ref "IC2") (pin "20") (pinfunction "MIC_N_20") (pintype "bidirectional"))
    )
    (net (code "89") (name "unconnected-(IC2A-MIC_P-Pad19)") (class "Default")
      (node (ref "IC2") (pin "19") (pinfunction "MIC_P_19") (pintype "bidirectional"))
    )
    (net (code "90") (name "unconnected-(IC2A-PWM1-Pad35)") (class "Default")
      (node (ref "IC2") (pin "35") (pinfunction "PWM1_35") (pintype "bidirectional"))
    )
    (net (code "91") (name "unconnected-(IC2A-PWM2-Pad36)") (class "Default")
      (node (ref "IC2") (pin "36") (pinfunction "PWM2_36") (pintype "bidirectional"))
    )
    (net (code "92") (name "unconnected-(IC2A-PWRKEY_OUT-Pad2)") (class "Default")
      (node (ref "IC2") (pin "2") (pinfunction "PWRKEY_OUT_2") (pintype "bidirectional"))
    )
    (net (code "93") (name "unconnected-(IC2A-RI-Pad4)") (class "Default")
      (node (ref "IC2") (pin "4") (pinfunction "RI_4") (pintype "bidirectional"))
    )
    (net (code "94") (name "unconnected-(IC2A-SCL-Pad38)") (class "Default")
      (node (ref "IC2") (pin "38") (pinfunction "SCL_38") (pintype "bidirectional"))
    )
    (net (code "95") (name "unconnected-(IC2A-SDA-Pad37)") (class "Default")
      (node (ref "IC2") (pin "37") (pinfunction "SDA_37") (pintype "bidirectional"))
    )
    (net (code "96") (name "unconnected-(IC2A-SPK_N-Pad22)") (class "Default")
      (node (ref "IC2") (pin "22") (pinfunction "SPK_N_22") (pintype "bidirectional"))
    )
    (net (code "97") (name "unconnected-(IC2A-SPK_P-Pad21)") (class "Default")
      (node (ref "IC2") (pin "21") (pinfunction "SPK_P_21") (pintype "bidirectional"))
    )
    (net (code "98") (name "unconnected-(IC3B-PA8-Pad29)") (class "Default")
      (node (ref "IC3") (pin "29") (pinfunction "PA8_29") (pintype "bidirectional"))
    )
    (net (code "99") (name "unconnected-(IC3B-PA15-Pad38)") (class "Default")
      (node (ref "IC3") (pin "38") (pinfunction "PA15_38") (pintype "bidirectional"))
    )
    (net (code "100") (name "unconnected-(IC3C-PA0-Pad10)") (class "Default")
      (node (ref "IC3") (pin "10") (pinfunction "PA0_10") (pintype "bidirectional"))
    )
    (net (code "101") (name "unconnected-(IC3C-PA1-Pad11)") (class "Default")
      (node (ref "IC3") (pin "11") (pinfunction "PA1_11") (pintype "bidirectional"))
    )
    (net (code "102") (name "unconnected-(IC3C-PA2-Pad12)") (class "Default")
      (node (ref "IC3") (pin "12") (pinfunction "PA2_12") (pintype "bidirectional"))
    )
    (net (code "103") (name "unconnected-(IC3D-PB8-Pad45)") (class "Default")
      (node (ref "IC3") (pin "45") (pinfunction "PB8_45") (pintype "bidirectional"))
    )
    (net (code "104") (name "unconnected-(IC3D-PB9-Pad46)") (class "Default")
      (node (ref "IC3") (pin "46") (pinfunction "PB9_46") (pintype "bidirectional"))
    )
    (net (code "105") (name "unconnected-(IC3D-PB12-Pad25)") (class "Default")
      (node (ref "IC3") (pin "25") (pinfunction "PB12_25") (pintype "bidirectional"))
    )
    (net (code "106") (name "unconnected-(IC3D-PB15-Pad28)") (class "Default")
      (node (ref "IC3") (pin "28") (pinfunction "PB15_28") (pintype "bidirectional"))
    )
    (net (code "107") (name "unconnected-(IC3E-PB0-Pad18)") (class "Default")
      (node (ref "IC3") (pin "18") (pinfunction "PB0_18") (pintype "bidirectional"))
    )
    (net (code "108") (name "unconnected-(IC3E-PB1-Pad19)") (class "Default")
      (node (ref "IC3") (pin "19") (pinfunction "PB1_19") (pintype "bidirectional"))
    )
    (net (code "109") (name "unconnected-(IC3E-PB3-Pad39)") (class "Default")
      (node (ref "IC3") (pin "39") (pinfunction "PB3_39") (pintype "bidirectional"))
    )
    (net (code "110") (name "unconnected-(IC3E-PB4-Pad40)") (class "Default")
      (node (ref "IC3") (pin "40") (pinfunction "PB4_40") (pintype "bidirectional"))
    )
    (net (code "111") (name "unconnected-(IC3F-PC13-Pad2)") (class "Default")
      (node (ref "IC3") (pin "2") (pinfunction "PC13_2") (pintype "bidirectional"))
    )
    (net (code "112") (name "unconnected-(IC3F-PC14-Pad3)") (class "Default")
      (node (ref "IC3") (pin "3") (pinfunction "PC14_3") (pintype "bidirectional"))
    )
    (net (code "113") (name "unconnected-(IC3F-PC15-Pad4)") (class "Default")
      (node (ref "IC3") (pin "4") (pinfunction "PC15_4") (pintype "bidirectional"))
    )
    (net (code "114") (name "unconnected-(J3-PadVPP)") (class "Default")
      (node (ref "J3") (pin "VPP") (pinfunction "VPP_VPP") (pintype "bidirectional"))
    )
    (net (code "115") (name "unconnected-(U$1-CD(1)-Pad9)") (class "Default")
      (node (ref "U$1") (pin "9") (pinfunction "CD(1)_9") (pintype "bidirectional"))
    )
    (net (code "116") (name "unconnected-(U$1-CD(2)-Pad10)") (class "Default")
      (node (ref "U$1") (pin "10") (pinfunction "CD(2)_10") (pintype "bidirectional"))
    )
    (net (code "117") (name "unconnected-(U$1-NC-Pad1)") (class "Default")
      (node (ref "U$1") (pin "1") (pinfunction "NC_1") (pintype "bidirectional"))
    )
    (net (code "118") (name "unconnected-(U$1-RSV-Pad8)") (class "Default")
      (node (ref "U$1") (pin "8") (pinfunction "RSV_8") (pintype "bidirectional"))
    )
    (net (code "119") (name "unconnected-(X1-Pad1)") (class "Default")
      (node (ref "X1") (pin "1") (pinfunction "1_1") (pintype "passive"))
    )
    (net (code "120") (name "unconnected-(X1-Pad4)") (class "Default")
      (node (ref "X1") (pin "4") (pinfunction "4_4") (pintype "passive"))
    )
    (net (code "121") (name "unconnected-(X1-Pad6)") (class "Default")
      (node (ref "X1") (pin "6") (pinfunction "6_6") (pintype "passive"))
    )
    (net (code "122") (name "unconnected-(X1-Pad9)") (class "Default")
      (node (ref "X1") (pin "9") (pinfunction "9_9") (pintype "passive"))
    )
  )
)
